# HyperRAM.net
KiCad netlist of a schematic drawn in Altium Designer
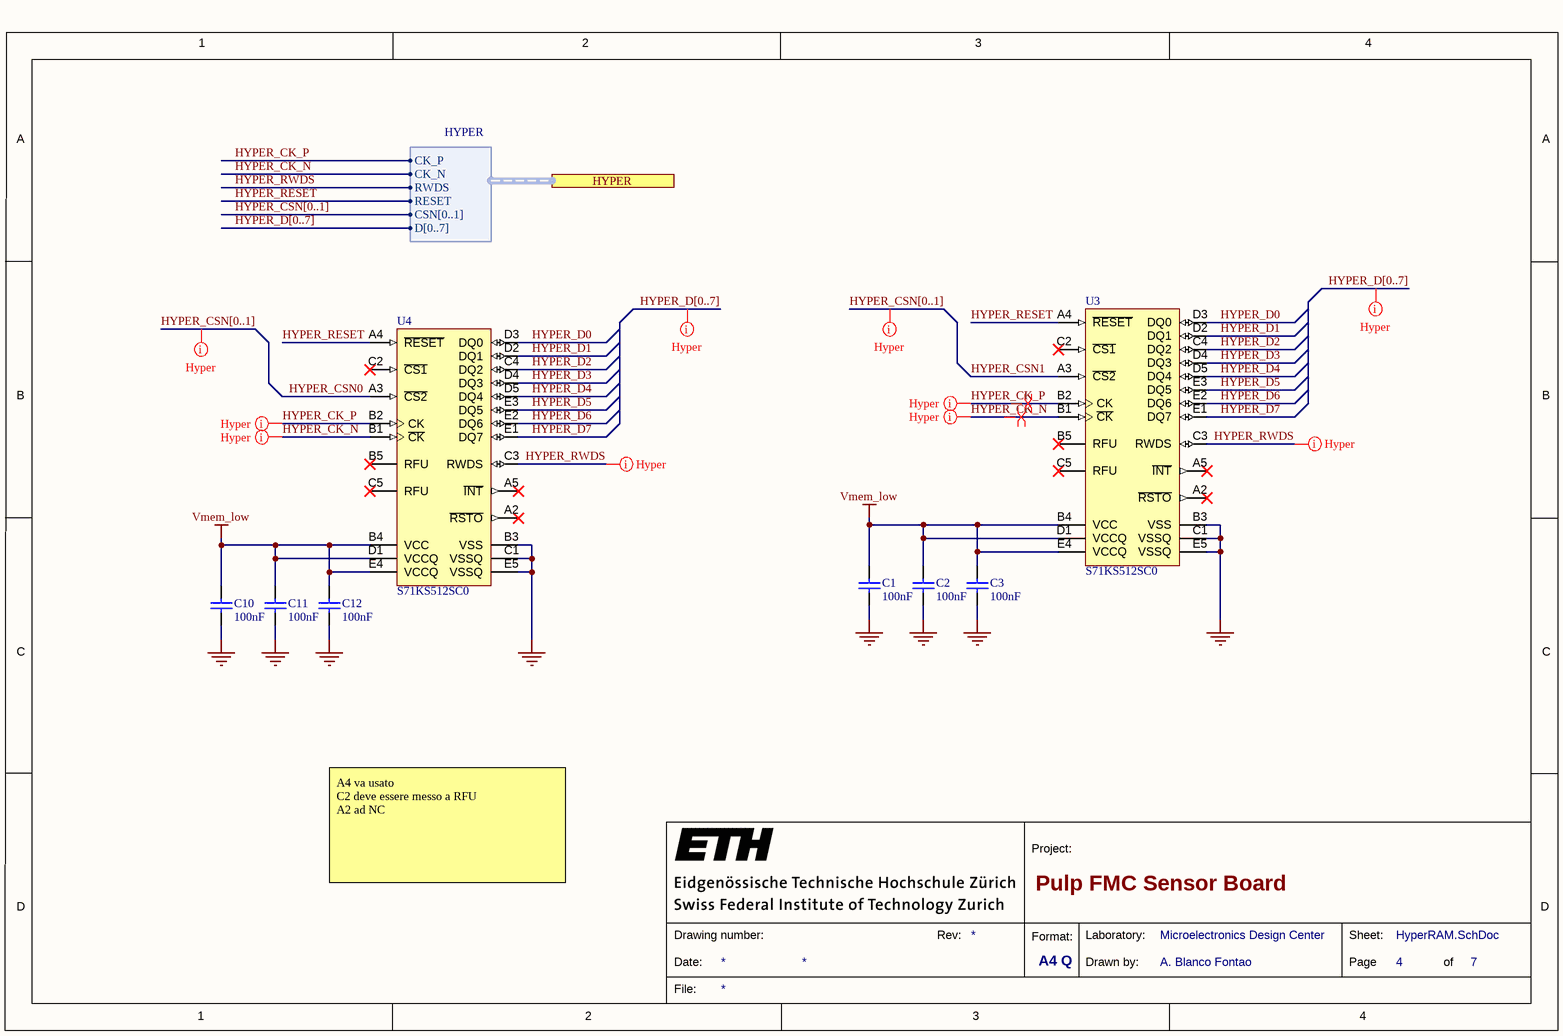
[diagram p0: HyperRAM.SchDoc]

(export (version "E")
  (design (tool "Eeschema 10.0.6"))
  (components
    (comp (ref "C1")
      (value "100nF")
      (footprint "CAPC0603(1608)100_N")
      (description "CAP 100nF 25V ±10% 0603 (1608 Metric) Thickness 1mm SMD")
      (fields (field (name "TOLERANCE") "Â±10%") (field (name "Comment") "CAP 100nF 25V 0603(1608)"))
      (libsource (lib "Altium Content Vault") (part "CMP-1035-02588-1"))
    )
    (comp (ref "C2")
      (value "100nF")
      (footprint "CAPC0603(1608)100_N")
      (description "CAP 100nF 25V ±10% 0603 (1608 Metric) Thickness 1mm SMD")
      (fields (field (name "TOLERANCE") "Â±10%") (field (name "Comment") "CAP 100nF 25V 0603(1608)"))
      (libsource (lib "Altium Content Vault") (part "CMP-1035-02588-1"))
    )
    (comp (ref "C3")
      (value "100nF")
      (footprint "CAPC0603(1608)100_N")
      (description "CAP 100nF 25V ±10% 0603 (1608 Metric) Thickness 1mm SMD")
      (fields (field (name "TOLERANCE") "Â±10%") (field (name "Comment") "CAP 100nF 25V 0603(1608)"))
      (libsource (lib "Altium Content Vault") (part "CMP-1035-02588-1"))
    )
    (comp (ref "C10")
      (value "100nF")
      (footprint "CAPC0603(1608)100_N")
      (description "CAP 100nF 25V ±10% 0603 (1608 Metric) Thickness 1mm SMD")
      (fields (field (name "TOLERANCE") "Â±10%") (field (name "Comment") "CAP 100nF 25V 0603(1608)"))
      (libsource (lib "Altium Content Vault") (part "CMP-1035-02588-1"))
    )
    (comp (ref "C11")
      (value "100nF")
      (footprint "CAPC0603(1608)100_N")
      (description "CAP 100nF 25V ±10% 0603 (1608 Metric) Thickness 1mm SMD")
      (fields (field (name "TOLERANCE") "Â±10%") (field (name "Comment") "CAP 100nF 25V 0603(1608)"))
      (libsource (lib "Altium Content Vault") (part "CMP-1035-02588-1"))
    )
    (comp (ref "C12")
      (value "100nF")
      (footprint "CAPC0603(1608)100_N")
      (description "CAP 100nF 25V ±10% 0603 (1608 Metric) Thickness 1mm SMD")
      (fields (field (name "TOLERANCE") "Â±10%") (field (name "Comment") "CAP 100nF 25V 0603(1608)"))
      (libsource (lib "Altium Content Vault") (part "CMP-1035-02588-1"))
    )
    (comp (ref "U3")
      (value "S71KS512SC0")
      (footprint "FBGA24_A-130")
      (description "IC 512MB FLASH 64MB DRAM 24FBGA")
      (fields (field (name "MANUFACTURER") "Cypress Semiconductor Corp"))
      (libsource (lib "Pulp FMC Sensor Board") (part "CMP-00514-1"))
    )
    (comp (ref "U4")
      (value "S71KS512SC0")
      (footprint "FBGA24_A-130")
      (description "IC 512MB FLASH 64MB DRAM 24FBGA")
      (fields (field (name "MANUFACTURER") "Cypress Semiconductor Corp"))
      (libsource (lib "ETHZ Vault") (part "S71KSxxxSC0"))
    )
  )
  (nets
    (net (code "2") (name "/HYPER_CK_N") (class "Default")
      (node (ref "U3") (pin "B1") (pinfunction "~{CK}_B1") (pintype "input"))
      (node (ref "U4") (pin "B1") (pinfunction "~{CK}_B1") (pintype "input"))
    )
    (net (code "3") (name "/HYPER_CK_P") (class "Default")
      (node (ref "U3") (pin "B2") (pinfunction "CK_B2") (pintype "input"))
      (node (ref "U4") (pin "B2") (pinfunction "CK_B2") (pintype "input"))
    )
    (net (code "4") (name "/HYPER_CSN0") (class "Default")
      (node (ref "U4") (pin "A3") (pinfunction "~{CS2}_A3") (pintype "input"))
    )
    (net (code "5") (name "/HYPER_CSN1") (class "Default")
      (node (ref "U3") (pin "A3") (pinfunction "~{CS2}_A3") (pintype "input"))
    )
    (net (code "7") (name "/HYPER_D0") (class "Default")
      (node (ref "U3") (pin "D3") (pinfunction "DQ0_D3") (pintype "bidirectional"))
      (node (ref "U4") (pin "D3") (pinfunction "DQ0_D3") (pintype "bidirectional"))
    )
    (net (code "8") (name "/HYPER_D1") (class "Default")
      (node (ref "U3") (pin "D2") (pinfunction "DQ1_D2") (pintype "bidirectional"))
      (node (ref "U4") (pin "D2") (pinfunction "DQ1_D2") (pintype "bidirectional"))
    )
    (net (code "9") (name "/HYPER_D2") (class "Default")
      (node (ref "U3") (pin "C4") (pinfunction "DQ2_C4") (pintype "bidirectional"))
      (node (ref "U4") (pin "C4") (pinfunction "DQ2_C4") (pintype "bidirectional"))
    )
    (net (code "10") (name "/HYPER_D3") (class "Default")
      (node (ref "U3") (pin "D4") (pinfunction "DQ3_D4") (pintype "bidirectional"))
      (node (ref "U4") (pin "D4") (pinfunction "DQ3_D4") (pintype "bidirectional"))
    )
    (net (code "11") (name "/HYPER_D4") (class "Default")
      (node (ref "U3") (pin "D5") (pinfunction "DQ4_D5") (pintype "bidirectional"))
      (node (ref "U4") (pin "D5") (pinfunction "DQ4_D5") (pintype "bidirectional"))
    )
    (net (code "12") (name "/HYPER_D5") (class "Default")
      (node (ref "U3") (pin "E3") (pinfunction "DQ5_E3") (pintype "bidirectional"))
      (node (ref "U4") (pin "E3") (pinfunction "DQ5_E3") (pintype "bidirectional"))
    )
    (net (code "13") (name "/HYPER_D6") (class "Default")
      (node (ref "U3") (pin "E2") (pinfunction "DQ6_E2") (pintype "bidirectional"))
      (node (ref "U4") (pin "E2") (pinfunction "DQ6_E2") (pintype "bidirectional"))
    )
    (net (code "14") (name "/HYPER_D7") (class "Default")
      (node (ref "U3") (pin "E1") (pinfunction "DQ7_E1") (pintype "bidirectional"))
      (node (ref "U4") (pin "E1") (pinfunction "DQ7_E1") (pintype "bidirectional"))
    )
    (net (code "16") (name "/HYPER_RESET") (class "Default")
      (node (ref "U3") (pin "A4") (pinfunction "~{RESET}_A4") (pintype "input"))
      (node (ref "U4") (pin "A4") (pinfunction "~{RESET}_A4") (pintype "input"))
    )
    (net (code "17") (name "/HYPER_RWDS") (class "Default")
      (node (ref "U3") (pin "C3") (pinfunction "RWDS_C3") (pintype "bidirectional"))
      (node (ref "U4") (pin "C3") (pinfunction "RWDS_C3") (pintype "bidirectional"))
    )
    (net (code "19") (name "GND") (class "Default")
      (node (ref "C1") (pin "1") (pinfunction "1_1") (pintype "passive"))
      (node (ref "C10") (pin "1") (pinfunction "1_1") (pintype "passive"))
      (node (ref "C11") (pin "1") (pinfunction "1_1") (pintype "passive"))
      (node (ref "C12") (pin "1") (pinfunction "1_1") (pintype "passive"))
      (node (ref "C2") (pin "1") (pinfunction "1_1") (pintype "passive"))
      (node (ref "C3") (pin "1") (pinfunction "1_1") (pintype "passive"))
      (node (ref "U3") (pin "B3") (pinfunction "VSS_B3") (pintype "power_in"))
      (node (ref "U3") (pin "C1") (pinfunction "VSSQ_C1") (pintype "power_in"))
      (node (ref "U3") (pin "E5") (pinfunction "VSSQ_E5") (pintype "power_in"))
      (node (ref "U4") (pin "B3") (pinfunction "VSS_B3") (pintype "power_in"))
      (node (ref "U4") (pin "C1") (pinfunction "VSSQ_C1") (pintype "power_in"))
      (node (ref "U4") (pin "E5") (pinfunction "VSSQ_E5") (pintype "power_in"))
    )
    (net (code "20") (name "Vmem_low") (class "Default")
      (node (ref "C1") (pin "2") (pinfunction "2_2") (pintype "passive"))
      (node (ref "C10") (pin "2") (pinfunction "2_2") (pintype "passive"))
      (node (ref "C11") (pin "2") (pinfunction "2_2") (pintype "passive"))
      (node (ref "C12") (pin "2") (pinfunction "2_2") (pintype "passive"))
      (node (ref "C2") (pin "2") (pinfunction "2_2") (pintype "passive"))
      (node (ref "C3") (pin "2") (pinfunction "2_2") (pintype "passive"))
      (node (ref "U3") (pin "B4") (pinfunction "VCC_B4") (pintype "power_in"))
      (node (ref "U3") (pin "D1") (pinfunction "VCCQ_D1") (pintype "power_in"))
      (node (ref "U3") (pin "E4") (pinfunction "VCCQ_E4") (pintype "power_in"))
      (node (ref "U4") (pin "B4") (pinfunction "VCC_B4") (pintype "power_in"))
      (node (ref "U4") (pin "D1") (pinfunction "VCCQ_D1") (pintype "power_in"))
      (node (ref "U4") (pin "E4") (pinfunction "VCCQ_E4") (pintype "power_in"))
    )
    (net (code "21") (name "unconnected-(U3-RFU-PadB5)") (class "Default")
      (node (ref "U3") (pin "B5") (pinfunction "RFU_B5") (pintype "passive+no_connect"))
    )
    (net (code "22") (name "unconnected-(U3-RFU-PadC5)") (class "Default")
      (node (ref "U3") (pin "C5") (pinfunction "RFU_C5") (pintype "passive+no_connect"))
    )
    (net (code "23") (name "unconnected-(U3-~{CS1}-PadC2)") (class "Default")
      (node (ref "U3") (pin "C2") (pinfunction "~{CS1}_C2") (pintype "input+no_connect"))
    )
    (net (code "24") (name "unconnected-(U3-~{INT}-PadA5)") (class "Default")
      (node (ref "U3") (pin "A5") (pinfunction "~{INT}_A5") (pintype "output+no_connect"))
    )
    (net (code "25") (name "unconnected-(U3-~{RSTO}-PadA2)") (class "Default")
      (node (ref "U3") (pin "A2") (pinfunction "~{RSTO}_A2") (pintype "output+no_connect"))
    )
    (net (code "26") (name "unconnected-(U4-RFU-PadB5)") (class "Default")
      (node (ref "U4") (pin "B5") (pinfunction "RFU_B5") (pintype "passive+no_connect"))
    )
    (net (code "27") (name "unconnected-(U4-RFU-PadC5)") (class "Default")
      (node (ref "U4") (pin "C5") (pinfunction "RFU_C5") (pintype "passive+no_connect"))
    )
    (net (code "28") (name "unconnected-(U4-~{CS1}-PadC2)") (class "Default")
      (node (ref "U4") (pin "C2") (pinfunction "~{CS1}_C2") (pintype "input+no_connect"))
    )
    (net (code "29") (name "unconnected-(U4-~{INT}-PadA5)") (class "Default")
      (node (ref "U4") (pin "A5") (pinfunction "~{INT}_A5") (pintype "output+no_connect"))
    )
    (net (code "30") (name "unconnected-(U4-~{RSTO}-PadA2)") (class "Default")
      (node (ref "U4") (pin "A2") (pinfunction "~{RSTO}_A2") (pintype "output+no_connect"))
    )
  )
)
